# CAN.net
KiCad netlist of a schematic drawn in Altium Designer
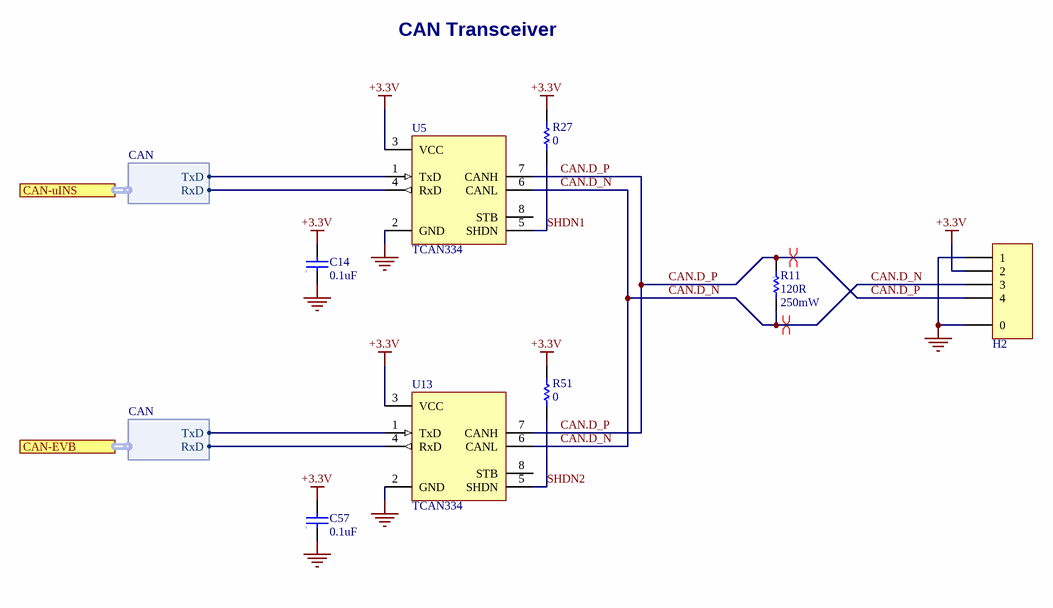
[diagram p0: CAN.SchDoc]

(export (version "E")
  (design (tool "Eeschema 10.0.6"))
  (components
    (comp (ref "C14")
      (value "0.1uF")
      (footprint "0402")
      (description "CAP CER .10UF 50V X7R 10% 0402")
      (fields
        (field (name "MANUFACTURER") "TDK Corporation")
        (field (name "MANUFACTURER PART NUMBER") "C1005X7R1H104K")
        (field (name "PUBLISHER") "Altium Limited")
      )
      (libsource (lib "General") (part "Cap"))
    )
    (comp (ref "C57")
      (value "0.1uF")
      (footprint "0402")
      (description "CAP CER .10UF 50V X7R 10% 0402")
      (fields
        (field (name "MANUFACTURER") "TDK Corporation")
        (field (name "MANUFACTURER PART NUMBER") "C1005X7R1H104K")
        (field (name "PUBLISHER") "Altium Limited")
      )
      (libsource (lib "General") (part "Cap"))
    )
    (comp (ref "H2")
      (value "Hdr - 4pin - mount")
      (footprint "SM04B-GHS-TB(LF)(SN)")
      (description "CONN HEADER GH SIDE 4POS 1.25MM")
      (fields
        (field (name "MANUFACTURER") "JST")
        (field (name "MANUFACTURER PART NUMBER") "SM04B-GHS-TB(LF)(SN)-")
      )
      (libsource (lib "Connectors") (part "Hdr - 4pin - mount"))
    )
    (comp (ref "R11")
      (value "120R")
      (footprint "R0603")
      (description "RES SMD 120 OHM 5% 1/4W 0603")
      (fields
        (field (name "MANUFACTURER") "Rohm")
        (field (name "MANUFACTURER PART NUMBER") "ESR03EZPJ121")
        (field (name "MAX POWER DISSIPATION") "250mW")
      )
      (libsource (lib "General") (part "Res"))
    )
    (comp (ref "R27")
      (value "0")
      (footprint "R0402")
      (description "RES SMD 0 OHM JUMPER 1/16W 0402")
      (fields
        (field (name "MANUFACTURER") "Yageo")
        (field (name "MANUFACTURER PART NUMBER") "RC0402JR-070RL")
      )
      (libsource (lib "General") (part "Res"))
    )
    (comp (ref "R51")
      (value "0")
      (footprint "R0402")
      (description "RES SMD 0 OHM JUMPER 1/16W 0402")
      (fields
        (field (name "MANUFACTURER") "Yageo")
        (field (name "MANUFACTURER PART NUMBER") "RC0402JR-070RL")
      )
      (libsource (lib "General") (part "Res"))
    )
    (comp (ref "U5")
      (value "TCAN334")
      (footprint "SOT23-8-65P280X145-8N")
      (description "IC TXRX CAN 3.3V SOT23-8")
      (fields
        (field (name "MANUFACTURER") "Texas Instruments")
        (field (name "MANUFACTURER PART NUMBER") "TCAN334DCNR")
      )
      (libsource (lib "ICs") (part "TCAN334"))
    )
    (comp (ref "U13")
      (value "TCAN334")
      (footprint "SOT23-8-65P280X145-8N")
      (description "IC TXRX CAN 3.3V SOT23-8")
      (fields
        (field (name "MANUFACTURER") "Texas Instruments")
        (field (name "MANUFACTURER PART NUMBER") "TCAN334DCNR")
      )
      (libsource (lib "ICs") (part "TCAN334"))
    )
  )
  (nets
    (net (code "2") (name "+3.3V") (class "Default")
      (node (ref "C14") (pin "2") (pinfunction "2_2") (pintype "passive"))
      (node (ref "C57") (pin "2") (pinfunction "2_2") (pintype "passive"))
      (node (ref "H2") (pin "2") (pinfunction "2_2") (pintype "passive"))
      (node (ref "R27") (pin "2") (pinfunction "2_2") (pintype "passive"))
      (node (ref "R51") (pin "2") (pinfunction "2_2") (pintype "passive"))
      (node (ref "U13") (pin "3") (pinfunction "VCC_3") (pintype "power_in"))
      (node (ref "U5") (pin "3") (pinfunction "VCC_3") (pintype "power_in"))
    )
    (net (code "3") (name "/CAN.D_N") (class "Default")
      (node (ref "H2") (pin "3") (pinfunction "3_3") (pintype "passive"))
      (node (ref "R11") (pin "2") (pinfunction "2_2") (pintype "passive"))
      (node (ref "U13") (pin "6") (pinfunction "CANL_6") (pintype "passive"))
      (node (ref "U5") (pin "6") (pinfunction "CANL_6") (pintype "passive"))
    )
    (net (code "4") (name "/CAN.D_P") (class "Default")
      (node (ref "H2") (pin "4") (pinfunction "4_4") (pintype "passive"))
      (node (ref "R11") (pin "1") (pinfunction "1_1") (pintype "passive"))
      (node (ref "U13") (pin "7") (pinfunction "CANH_7") (pintype "passive"))
      (node (ref "U5") (pin "7") (pinfunction "CANH_7") (pintype "passive"))
    )
    (net (code "5") (name "/SHDN1") (class "Default")
      (node (ref "R27") (pin "1") (pinfunction "1_1") (pintype "passive"))
      (node (ref "U5") (pin "5") (pinfunction "SHDN_5") (pintype "passive"))
    )
    (net (code "6") (name "/SHDN2") (class "Default")
      (node (ref "R51") (pin "1") (pinfunction "1_1") (pintype "passive"))
      (node (ref "U13") (pin "5") (pinfunction "SHDN_5") (pintype "passive"))
    )
    (net (code "8") (name "GND") (class "Default")
      (node (ref "C14") (pin "1") (pinfunction "1_1") (pintype "passive"))
      (node (ref "C57") (pin "1") (pinfunction "1_1") (pintype "passive"))
      (node (ref "H2") (pin "0") (pinfunction "0_0") (pintype "passive"))
      (node (ref "H2") (pin "1") (pinfunction "1_1") (pintype "passive"))
      (node (ref "U13") (pin "2") (pinfunction "GND_2") (pintype "power_in"))
      (node (ref "U5") (pin "2") (pinfunction "GND_2") (pintype "power_in"))
    )
    (net (code "9") (name "unconnected-(U5-RxD-Pad4)") (class "Default")
      (node (ref "U5") (pin "4") (pinfunction "RxD_4") (pintype "output"))
    )
    (net (code "10") (name "unconnected-(U5-STB-Pad8)") (class "Default")
      (node (ref "U5") (pin "8") (pinfunction "STB_8") (pintype "passive"))
    )
    (net (code "11") (name "unconnected-(U5-TxD-Pad1)") (class "Default")
      (node (ref "U5") (pin "1") (pinfunction "TxD_1") (pintype "input"))
    )
    (net (code "12") (name "unconnected-(U13-RxD-Pad4)") (class "Default")
      (node (ref "U13") (pin "4") (pinfunction "RxD_4") (pintype "output"))
    )
    (net (code "13") (name "unconnected-(U13-STB-Pad8)") (class "Default")
      (node (ref "U13") (pin "8") (pinfunction "STB_8") (pintype "passive"))
    )
    (net (code "14") (name "unconnected-(U13-TxD-Pad1)") (class "Default")
      (node (ref "U13") (pin "1") (pinfunction "TxD_1") (pintype "input"))
    )
  )
)
